# AirDistMotor.net
KiCad netlist of a schematic drawn in EAGLE
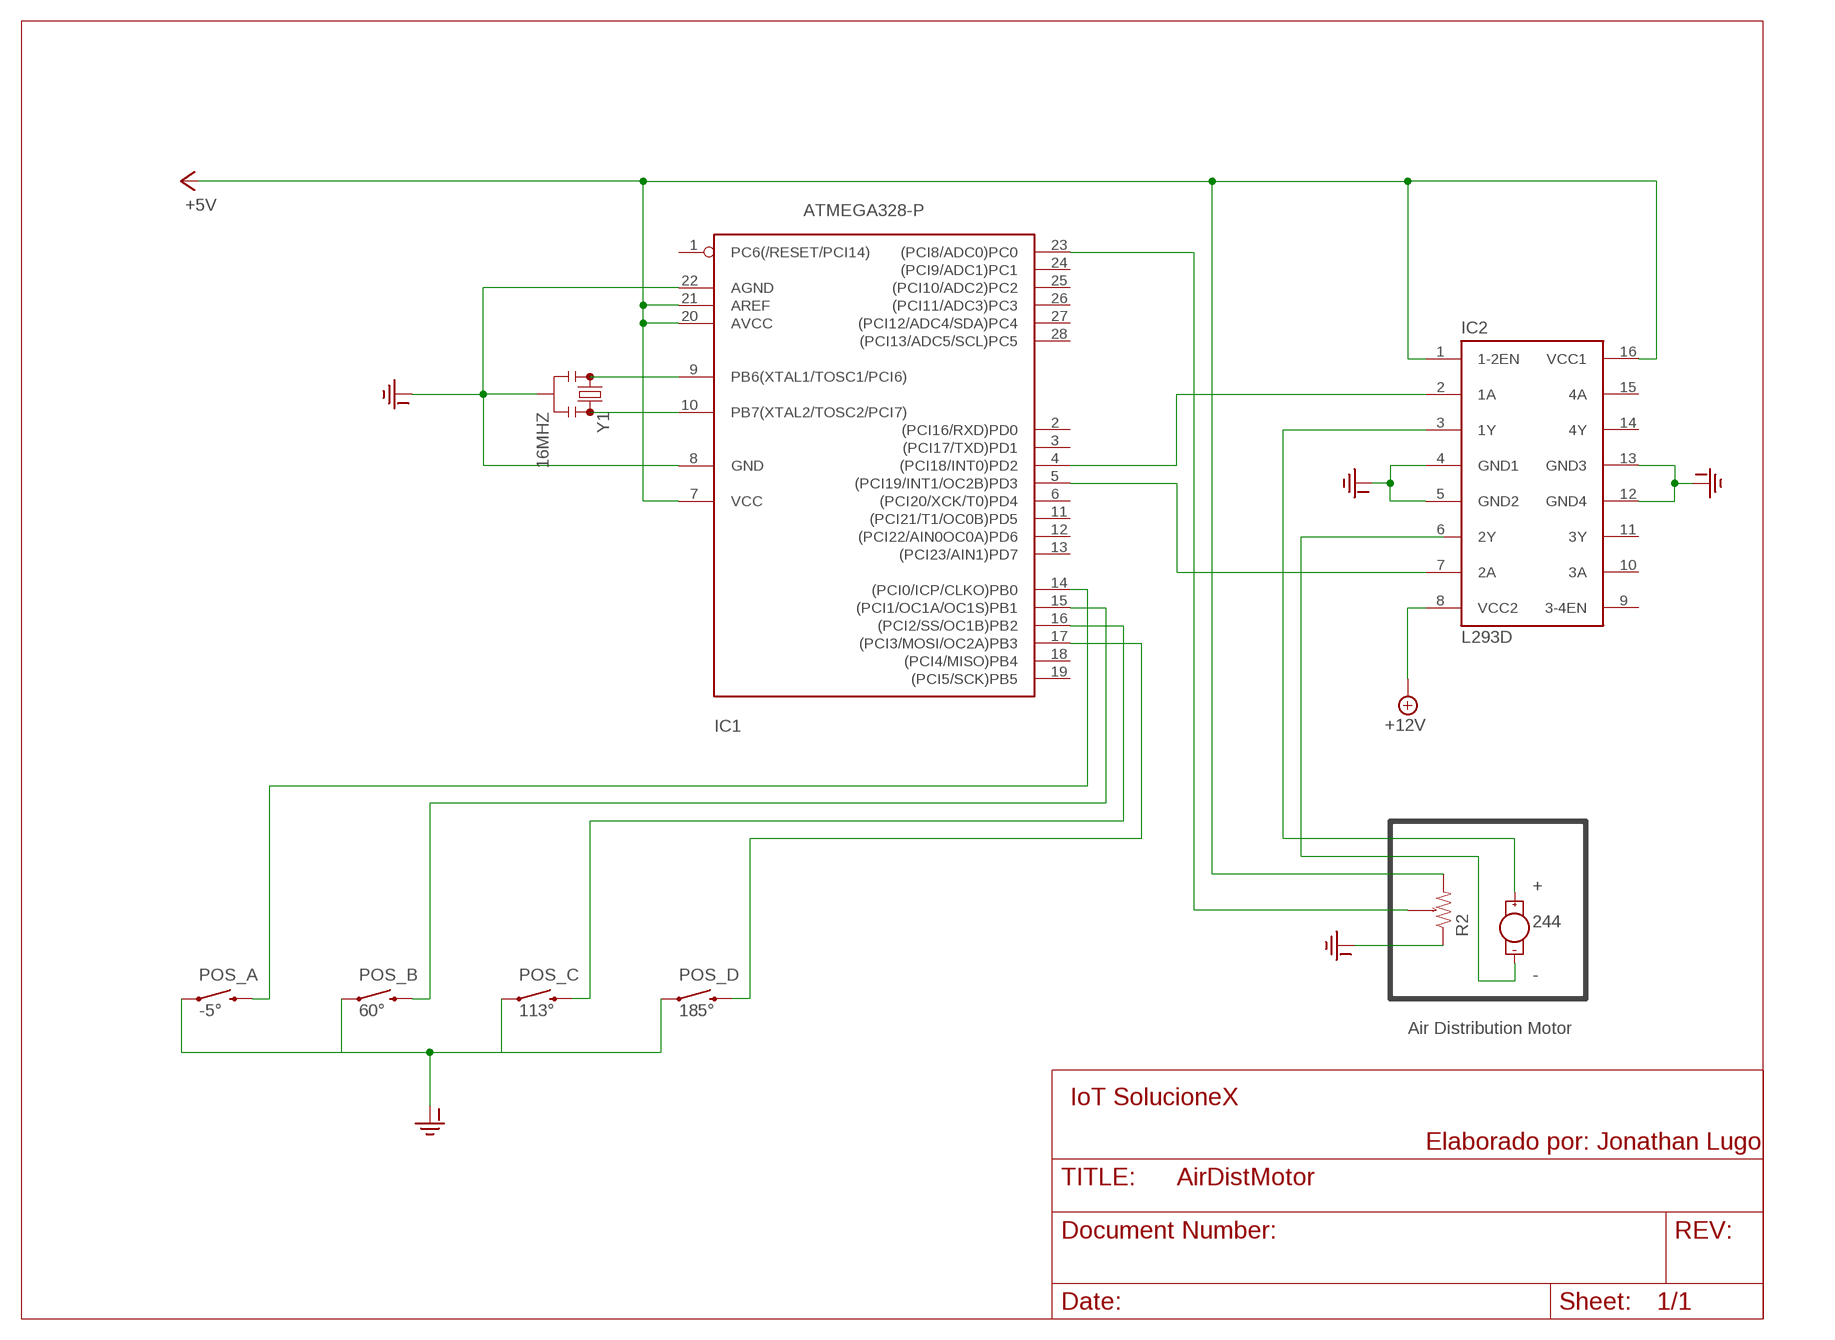
[diagram p0: schematic, sheet 1]

(export (version "E")
  (design (tool "Eeschema 10.0.6"))
  (components
    (comp (ref "244")
      (value "MOTOR10MM")
      (footprint "eagle-import:VIBE-MOTOR-10MM")
      (libsource (lib "eagle-import") (part "MOTOR10MM"))
    )
    (comp (ref "IC1")
      (value "ATMEGA328-P")
      (footprint "eagle-import:DIL28-3")
      (libsource (lib "eagle-import") (part "ATMEGA328P-20"))
    )
    (comp (ref "IC2")
      (value "L293D")
      (footprint "eagle-import:DIL16")
      (libsource (lib "eagle-import") (part "L293D"))
    )
    (comp (ref "POS_A")
      (value "-5°")
      (footprint "eagle-import:TACTILE-PTH")
      (libsource (lib "eagle-import") (part "SWITCH-MOMENTARY-2PTH"))
    )
    (comp (ref "POS_B")
      (value "60°")
      (footprint "eagle-import:TACTILE-PTH")
      (libsource (lib "eagle-import") (part "SWITCH-MOMENTARY-2PTH"))
    )
    (comp (ref "POS_C")
      (value "113°")
      (footprint "eagle-import:TACTILE-PTH")
      (libsource (lib "eagle-import") (part "SWITCH-MOMENTARY-2PTH"))
    )
    (comp (ref "POS_D")
      (value "185°")
      (footprint "eagle-import:TACTILE-PTH")
      (libsource (lib "eagle-import") (part "SWITCH-MOMENTARY-2PTH"))
    )
    (comp (ref "R2")
      (value "POTENTIOMETER")
      (footprint "eagle-import:0603-ARV")
      (libsource (lib "eagle-import") (part "POTENTIOMETER"))
    )
    (comp (ref "Y1")
      (value "16MHZ")
      (footprint "eagle-import:RESONATOR-SMD")
      (libsource (lib "eagle-import") (part "RESONATOR16MHZ"))
    )
  )
  (nets
    (net (code "1") (name "+5V") (class "Default")
      (node (ref "IC1") (pin "20") (pinfunction "AVCC_20") (pintype "bidirectional"))
      (node (ref "IC1") (pin "21") (pinfunction "AREF_21") (pintype "bidirectional"))
      (node (ref "IC1") (pin "7") (pinfunction "VCC_7") (pintype "bidirectional"))
      (node (ref "IC2") (pin "1") (pinfunction "1-2EN_1") (pintype "input"))
      (node (ref "IC2") (pin "16") (pinfunction "VCC1_16") (pintype "power_in"))
      (node (ref "R2") (pin "2") (pinfunction "2_2") (pintype "passive"))
    )
    (net (code "2") (name "+12V") (class "Default")
      (node (ref "IC2") (pin "8") (pinfunction "VCC2_8") (pintype "power_in"))
    )
    (net (code "3") (name "GND-ISO") (class "Default")
      (node (ref "IC1") (pin "22") (pinfunction "AGND_22") (pintype "bidirectional"))
      (node (ref "IC1") (pin "8") (pinfunction "GND_8") (pintype "bidirectional"))
      (node (ref "IC2") (pin "12") (pinfunction "GND4_12") (pintype "power_in"))
      (node (ref "IC2") (pin "13") (pinfunction "GND3_13") (pintype "power_in"))
      (node (ref "IC2") (pin "4") (pinfunction "GND1_4") (pintype "power_in"))
      (node (ref "IC2") (pin "5") (pinfunction "GND2_5") (pintype "power_in"))
      (node (ref "POS_A") (pin "1") (pinfunction "1_1") (pintype "passive"))
      (node (ref "POS_D") (pin "1") (pinfunction "1_1") (pintype "passive"))
      (node (ref "R2") (pin "1") (pinfunction "1_1") (pintype "passive"))
      (node (ref "Y1") (pin "2") (pinfunction "2_2") (pintype "passive"))
    )
    (net (code "4") (name "Net-(IC1-(PCI0{slash}ICP{slash}CLKO)PB0)") (class "Default")
      (node (ref "IC1") (pin "14") (pinfunction "(PCI0/ICP/CLKO)PB0_14") (pintype "bidirectional"))
      (node (ref "POS_A") (pin "3") (pinfunction "2_3") (pintype "passive"))
    )
    (net (code "5") (name "Net-(IC1-(PCI1{slash}OC1A{slash}OC1S)PB1)") (class "Default")
      (node (ref "IC1") (pin "15") (pinfunction "(PCI1/OC1A/OC1S)PB1_15") (pintype "bidirectional"))
      (node (ref "POS_B") (pin "3") (pinfunction "2_3") (pintype "passive"))
    )
    (net (code "6") (name "Net-(IC1-(PCI2{slash}SS{slash}OC1B)PB2)") (class "Default")
      (node (ref "IC1") (pin "16") (pinfunction "(PCI2/SS/OC1B)PB2_16") (pintype "bidirectional"))
      (node (ref "POS_C") (pin "3") (pinfunction "2_3") (pintype "passive"))
    )
    (net (code "7") (name "Net-(IC1-(PCI3{slash}MOSI{slash}OC2A)PB3)") (class "Default")
      (node (ref "IC1") (pin "17") (pinfunction "(PCI3/MOSI/OC2A)PB3_17") (pintype "bidirectional"))
      (node (ref "POS_D") (pin "3") (pinfunction "2_3") (pintype "passive"))
    )
    (net (code "8") (name "Net-(IC1-(PCI8{slash}ADC0)PC0)") (class "Default")
      (node (ref "IC1") (pin "23") (pinfunction "(PCI8/ADC0)PC0_23") (pintype "bidirectional"))
      (node (ref "R2") (pin "3") (pinfunction "P$1_3") (pintype "bidirectional"))
      (node (ref "R2") (pin "4") (pinfunction "P$1_4") (pintype "bidirectional"))
      (node (ref "R2") (pin "5") (pinfunction "P$1_5") (pintype "bidirectional"))
      (node (ref "R2") (pin "6") (pinfunction "P$1_6") (pintype "bidirectional"))
      (node (ref "R2") (pin "7") (pinfunction "P$1_7") (pintype "bidirectional"))
      (node (ref "R2") (pin "8") (pinfunction "P$1_8") (pintype "bidirectional"))
    )
    (net (code "9") (name "Net-(IC1-(PCI18{slash}INT0)PD2)") (class "Default")
      (node (ref "IC1") (pin "4") (pinfunction "(PCI18/INT0)PD2_4") (pintype "bidirectional"))
      (node (ref "IC2") (pin "2") (pinfunction "1A_2") (pintype "input"))
    )
    (net (code "10") (name "Net-(IC1-(PCI19{slash}INT1{slash}OC2B)PD3)") (class "Default")
      (node (ref "IC1") (pin "5") (pinfunction "(PCI19/INT1/OC2B)PD3_5") (pintype "bidirectional"))
      (node (ref "IC2") (pin "7") (pinfunction "2A_7") (pintype "input"))
    )
    (net (code "11") (name "Net-(IC1-PB6(XTAL1{slash}TOSC1{slash}PCI6))") (class "Default")
      (node (ref "IC1") (pin "9") (pinfunction "PB6(XTAL1/TOSC1/PCI6)_9") (pintype "bidirectional"))
      (node (ref "Y1") (pin "1") (pinfunction "1_1") (pintype "passive"))
    )
    (net (code "12") (name "Net-(IC1-PB7(XTAL2{slash}TOSC2{slash}PCI7))") (class "Default")
      (node (ref "IC1") (pin "10") (pinfunction "PB7(XTAL2/TOSC2/PCI7)_10") (pintype "bidirectional"))
      (node (ref "Y1") (pin "3") (pinfunction "3_3") (pintype "passive"))
    )
    (net (code "13") (name "Net-(IC2-1Y)") (class "Default")
      (node (ref "244") (pin "+") (pinfunction "+_+") (pintype "bidirectional"))
      (node (ref "IC2") (pin "3") (pinfunction "1Y_3") (pintype "output"))
    )
    (net (code "14") (name "unconnected-(244-Pad-)") (class "Default")
      (node (ref "244") (pin "-") (pinfunction "-_-") (pintype "bidirectional"))
    )
    (net (code "15") (name "unconnected-(IC1-(PCI4{slash}MISO)PB4-Pad18)") (class "Default")
      (node (ref "IC1") (pin "18") (pinfunction "(PCI4/MISO)PB4_18") (pintype "bidirectional"))
    )
    (net (code "16") (name "unconnected-(IC1-(PCI5{slash}SCK)PB5-Pad19)") (class "Default")
      (node (ref "IC1") (pin "19") (pinfunction "(PCI5/SCK)PB5_19") (pintype "bidirectional"))
    )
    (net (code "17") (name "unconnected-(IC1-(PCI9{slash}ADC1)PC1-Pad24)") (class "Default")
      (node (ref "IC1") (pin "24") (pinfunction "(PCI9/ADC1)PC1_24") (pintype "bidirectional"))
    )
    (net (code "18") (name "unconnected-(IC1-(PCI10{slash}ADC2)PC2-Pad25)") (class "Default")
      (node (ref "IC1") (pin "25") (pinfunction "(PCI10/ADC2)PC2_25") (pintype "bidirectional"))
    )
    (net (code "19") (name "unconnected-(IC1-(PCI11{slash}ADC3)PC3-Pad26)") (class "Default")
      (node (ref "IC1") (pin "26") (pinfunction "(PCI11/ADC3)PC3_26") (pintype "bidirectional"))
    )
    (net (code "20") (name "unconnected-(IC1-(PCI12{slash}ADC4{slash}SDA)PC4-Pad27)") (class "Default")
      (node (ref "IC1") (pin "27") (pinfunction "(PCI12/ADC4/SDA)PC4_27") (pintype "bidirectional"))
    )
    (net (code "21") (name "unconnected-(IC1-(PCI13{slash}ADC5{slash}SCL)PC5-Pad28)") (class "Default")
      (node (ref "IC1") (pin "28") (pinfunction "(PCI13/ADC5/SCL)PC5_28") (pintype "bidirectional"))
    )
    (net (code "22") (name "unconnected-(IC1-(PCI16{slash}RXD)PD0-Pad2)") (class "Default")
      (node (ref "IC1") (pin "2") (pinfunction "(PCI16/RXD)PD0_2") (pintype "bidirectional"))
    )
    (net (code "23") (name "unconnected-(IC1-(PCI17{slash}TXD)PD1-Pad3)") (class "Default")
      (node (ref "IC1") (pin "3") (pinfunction "(PCI17/TXD)PD1_3") (pintype "bidirectional"))
    )
    (net (code "24") (name "unconnected-(IC1-(PCI20{slash}XCK{slash}T0)PD4-Pad6)") (class "Default")
      (node (ref "IC1") (pin "6") (pinfunction "(PCI20/XCK/T0)PD4_6") (pintype "bidirectional"))
    )
    (net (code "25") (name "unconnected-(IC1-(PCI21{slash}T1{slash}OC0B)PD5-Pad11)") (class "Default")
      (node (ref "IC1") (pin "11") (pinfunction "(PCI21/T1/OC0B)PD5_11") (pintype "bidirectional"))
    )
    (net (code "26") (name "unconnected-(IC1-(PCI22{slash}AIN0OC0A)PD6-Pad12)") (class "Default")
      (node (ref "IC1") (pin "12") (pinfunction "(PCI22/AIN0OC0A)PD6_12") (pintype "bidirectional"))
    )
    (net (code "27") (name "unconnected-(IC1-(PCI23{slash}AIN1)PD7-Pad13)") (class "Default")
      (node (ref "IC1") (pin "13") (pinfunction "(PCI23/AIN1)PD7_13") (pintype "bidirectional"))
    )
    (net (code "28") (name "unconnected-(IC1-PC6({slash}RESET{slash}PCI14)-Pad1)") (class "Default")
      (node (ref "IC1") (pin "1") (pinfunction "PC6(/RESET/PCI14)_1") (pintype "bidirectional"))
    )
    (net (code "29") (name "unconnected-(IC2-2Y-Pad6)") (class "Default")
      (node (ref "IC2") (pin "6") (pinfunction "2Y_6") (pintype "output"))
    )
    (net (code "30") (name "unconnected-(IC2-3-4EN-Pad9)") (class "Default")
      (node (ref "IC2") (pin "9") (pinfunction "3-4EN_9") (pintype "input"))
    )
    (net (code "31") (name "unconnected-(IC2-3A-Pad10)") (class "Default")
      (node (ref "IC2") (pin "10") (pinfunction "3A_10") (pintype "input"))
    )
    (net (code "32") (name "unconnected-(IC2-3Y-Pad11)") (class "Default")
      (node (ref "IC2") (pin "11") (pinfunction "3Y_11") (pintype "output"))
    )
    (net (code "33") (name "unconnected-(IC2-4A-Pad15)") (class "Default")
      (node (ref "IC2") (pin "15") (pinfunction "4A_15") (pintype "input"))
    )
    (net (code "34") (name "unconnected-(IC2-4Y-Pad14)") (class "Default")
      (node (ref "IC2") (pin "14") (pinfunction "4Y_14") (pintype "output"))
    )
    (net (code "35") (name "unconnected-(POS_B-Pad1)") (class "Default")
      (node (ref "POS_B") (pin "1") (pinfunction "1_1") (pintype "passive"))
    )
    (net (code "36") (name "unconnected-(POS_C-Pad1)") (class "Default")
      (node (ref "POS_C") (pin "1") (pinfunction "1_1") (pintype "passive"))
    )
  )
)
